# BUCK_Converter.net
KiCad netlist of a schematic drawn in Altium Designer
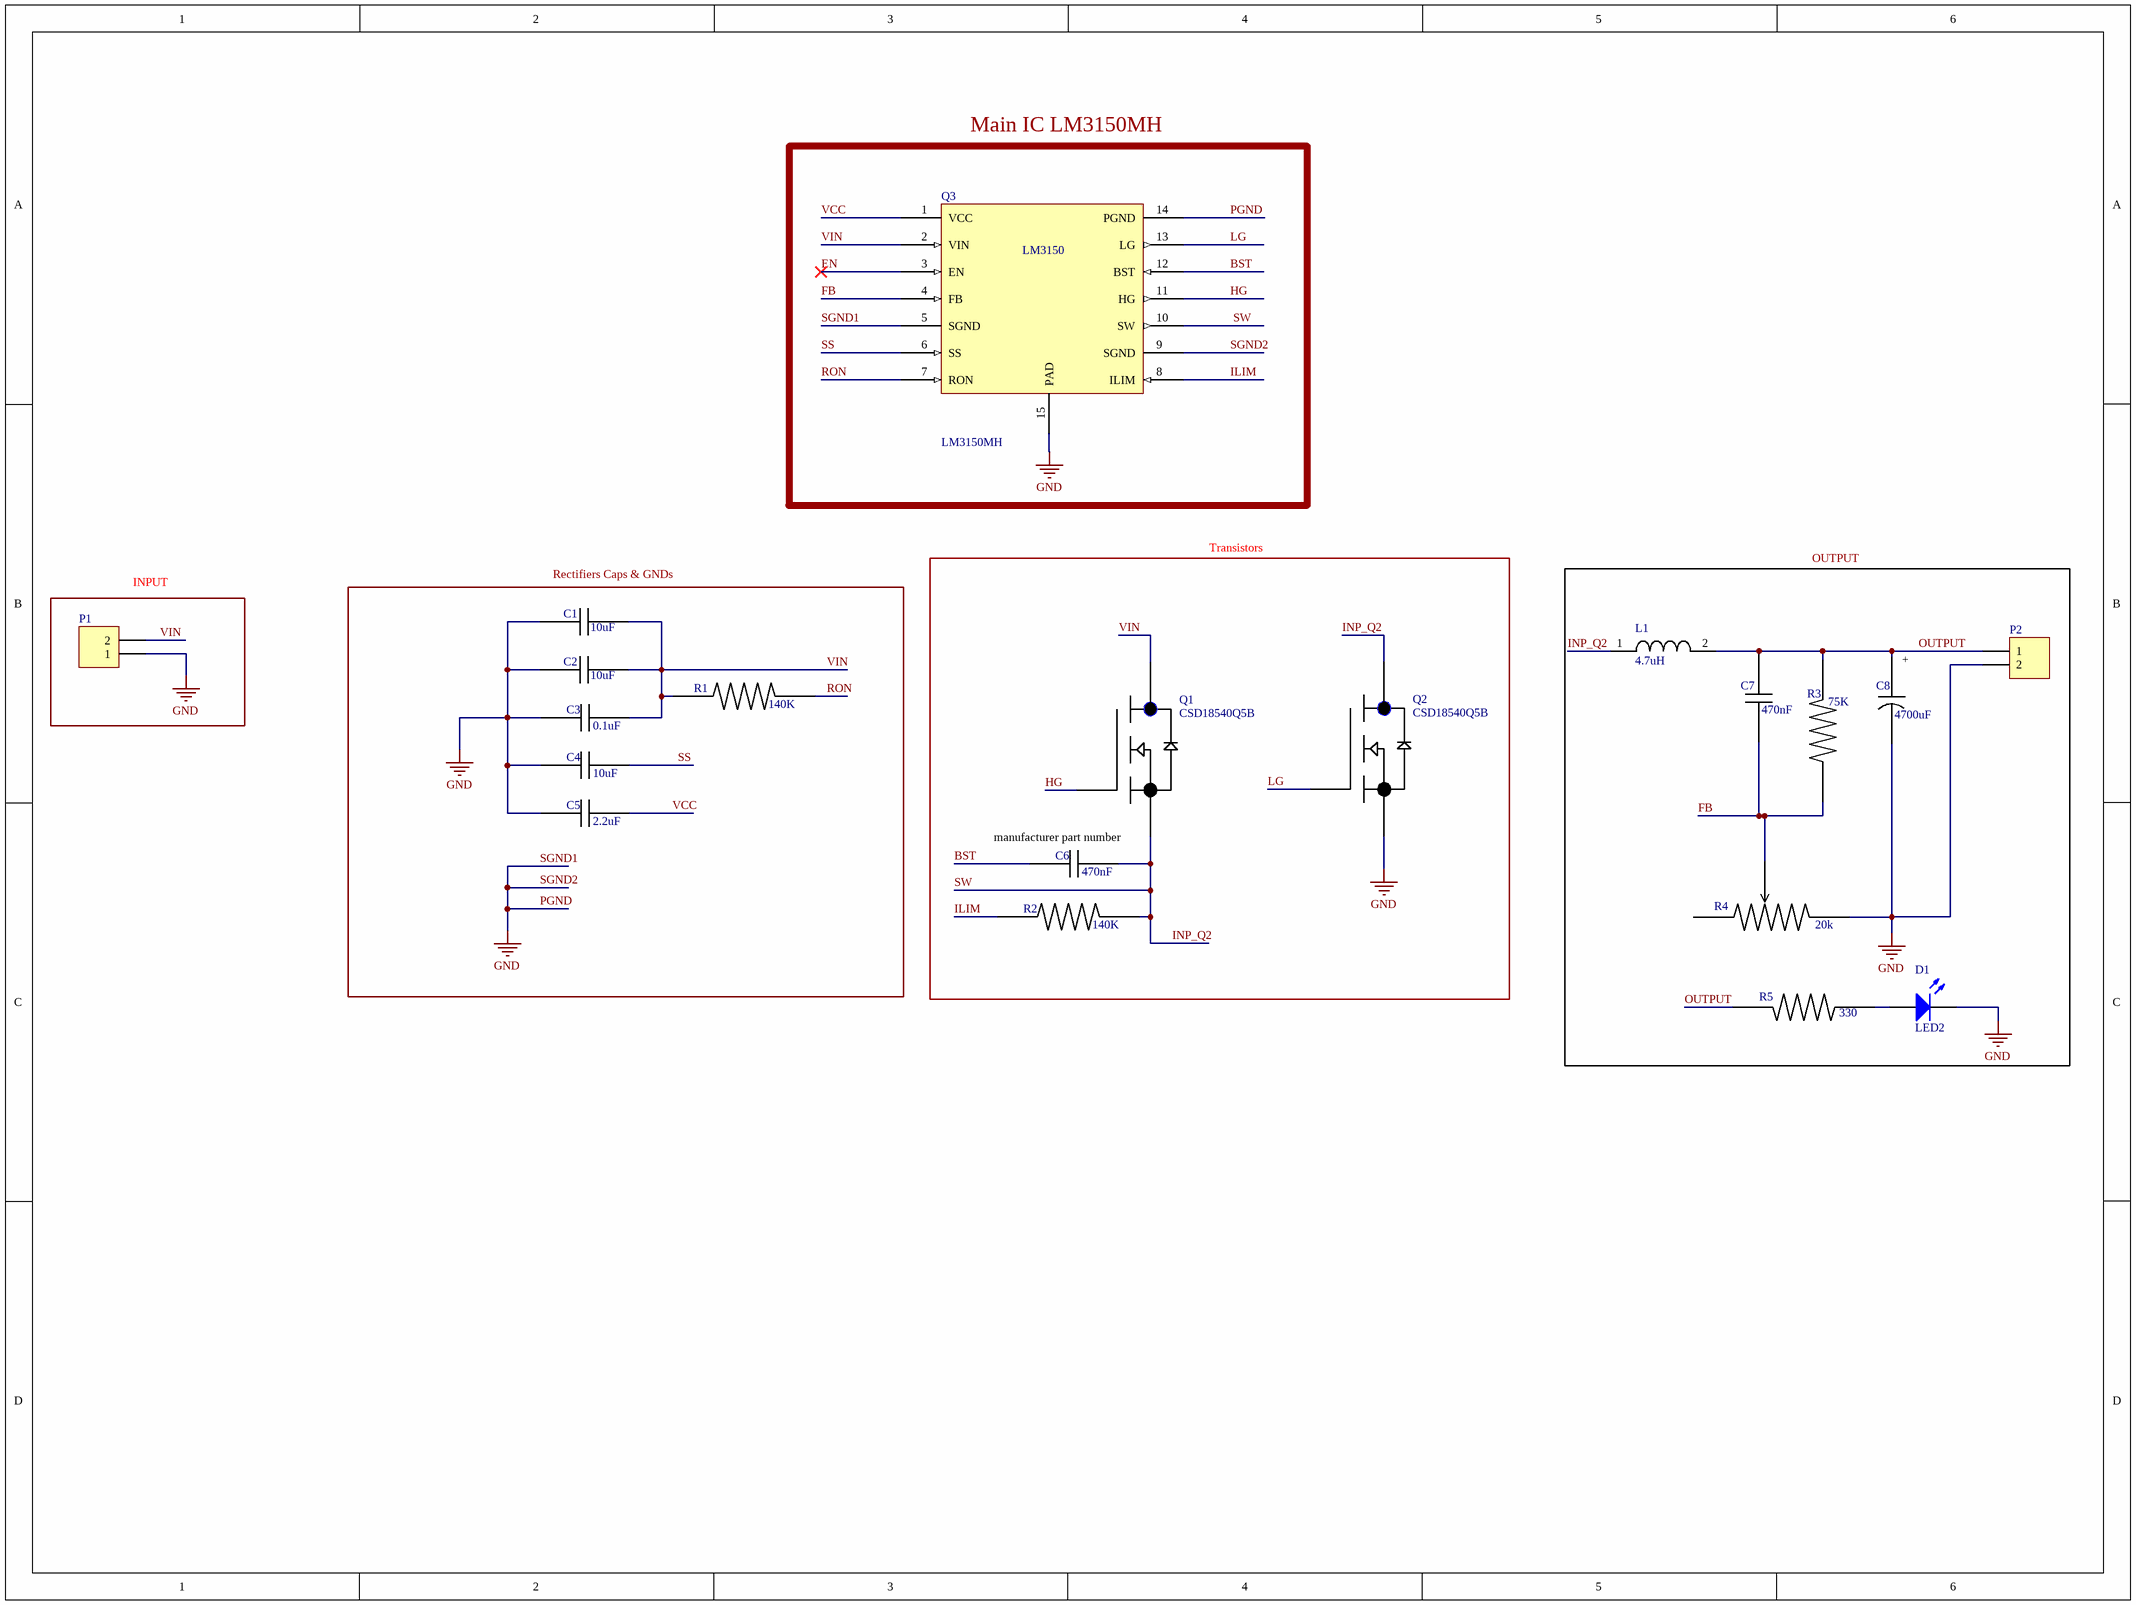
[diagram p0: BUCK_Converter.SchDoc]

(export (version "E")
  (design (tool "Eeschema 10.0.6"))
  (components
    (comp (ref "C1")
      (value "10uF")
      (footprint "1206_cap")
      (description "CAP CER 10UF 16V X5R 1206")
      (fields (field (name "MF") "Samsung Electro-Mechanics"))
      (libsource (lib "components_for_last_time") (part "Capacitor"))
    )
    (comp (ref "C2")
      (value "10uF")
      (footprint "1206_cap")
      (description "CAP CER 10UF 16V X5R 1206")
      (fields (field (name "MF") "Samsung Electro-Mechanics"))
      (libsource (lib "components_for_last_time") (part "Capacitor"))
    )
    (comp (ref "C3")
      (value "0.1uF")
      (footprint "1206_cap")
      (description "CAP CER 0.1UF 50V X7R 1206")
      (fields (field (name "MF") "Samsung Electro-Mechanics"))
      (libsource (lib "Buck comp.") (part "Capacitor_smd"))
    )
    (comp (ref "C4")
      (value "10uF")
      (footprint "1206_cap")
      (description "CAP CER 10UF 16V X5R 1206")
      (fields (field (name "MF") "Samsung Electro-Mechanics"))
      (libsource (lib "Buck comp.") (part "Capacitor_smd"))
    )
    (comp (ref "C5")
      (value "2.2uF")
      (footprint "1206_cap")
      (description "CAP CER 2.2UF 16V X7R 1206")
      (fields (field (name "MF") "Samsung Electro-Mechanics"))
      (libsource (lib "Buck comp.") (part "Capacitor_smd"))
    )
    (comp (ref "C6")
      (value "470nF")
      (footprint "1206_cap")
      (description "CAP CER 0.047UF 50V X7R 1206")
      (fields (field (name "MF") "Samsung Electro-Mechanics"))
      (libsource (lib "Buck comp.") (part "Capacitor_smd"))
    )
    (comp (ref "C7")
      (value "470nF")
      (footprint "1206_cap")
      (description "CAP CER 0.047UF 50V X7R 1206")
      (fields (field (name "MF") "Samsung Electro-Mechanics"))
      (libsource (lib "Buck comp.") (part "Capacitor_smd"))
    )
    (comp (ref "C8")
      (value "4700uF")
      (footprint "CAp")
      (description "CAP ALUM 4700UF 20% 10V SMD")
      (fields (field (name "MF") "Panasonic"))
      (libsource (lib "components_for_last_time") (part "Capacitor_al"))
    )
    (comp (ref "D1")
      (value "LED2")
      (footprint "3.2X1.6X1.1")
      (description "Typical RED, GREEN, YELLOW, AMBER GaAs LED")
      (libsource (lib "Miscellaneous Devices") (part "LED2"))
    )
    (comp (ref "L1")
      (value "4.7uH")
      (footprint "coill")
      (description "FIXED IND 4.7UH 3A 40.3 MOHM SMD")
      (fields (field (name "MF") "Taiyo Yuden"))
      (libsource (lib "components_for_last_time") (part "Coil"))
    )
    (comp (ref "P1")
      (value "Header 2")
      (footprint "HDR1X2")
      (description "Header, 2-Pin")
      (libsource (lib "") (part "Header 2_1"))
    )
    (comp (ref "P2")
      (value "Header 2")
      (footprint "HDR1X2")
      (description "Header, 2-Pin")
      (libsource (lib "Miscellaneous Connectors") (part "Header 2"))
    )
    (comp (ref "Q1")
      (value "CSD18540Q5B")
      (footprint "CSD18540Q5B")
      (description "MOSFET N-CH 60V 100A 8VSON")
      (fields (field (name "MF") "Texas Instruments"))
      (libsource (lib "Buck comp.") (part "CSD18540Q5B"))
    )
    (comp (ref "Q2")
      (value "CSD18540Q5B")
      (footprint "CSD18540Q5B")
      (description "MOSFET N-CH 60V 100A 8VSON")
      (fields (field (name "MF") "Texas Instruments"))
      (libsource (lib "Buck comp.") (part "CSD18540Q5B"))
    )
    (comp (ref "Q3")
      (value "LM3150MH")
      (footprint "LM3150MH")
      (description "IC REG CTRLR BUCK 14TSSOP")
      (fields (field (name "MF") "Texas Instruments"))
      (libsource (lib "components_for_last_time") (part "LM3150MH"))
    )
    (comp (ref "R1")
      (value "140K")
      (footprint "1206_res")
      (description "RES SMD 140K OHM 1% 1/4W 1206")
      (fields (field (name "MF") "Vishay Dale"))
      (libsource (lib "Buck comp.") (part "resistor_smd"))
    )
    (comp (ref "R2")
      (value "140K")
      (footprint "1206_res")
      (description "RES SMD 140K OHM 1% 1/4W 1206")
      (fields (field (name "MF") "Vishay Dale"))
      (libsource (lib "Buck comp.") (part "resistor_smd"))
    )
    (comp (ref "R3")
      (value "75K")
      (footprint "1206_res")
      (description "RES SMD 75K OHM 1% 1/20W 0201")
      (fields (field (name "MF") "Vishay Dale"))
      (libsource (lib "Buck comp.") (part "resistor_smd"))
    )
    (comp (ref "R4")
      (value "20k")
      (footprint "pot_smd")
      (description "20 kOhms 0.5W, 1/2W Gull Wing Surface Mount Trimmer Potentiometer Cermet 1.0 Turn Top Adjustment")
      (fields (field (name "MF") "Bourns Inc."))
      (libsource (lib "components_for_last_time") (part "pot"))
    )
    (comp (ref "R5")
      (value "330")
      (footprint "1206_res")
      (description "RES SMD 330 OHM 1% 1/20W 0201")
      (fields (field (name "MF") "Vishay Dale"))
      (libsource (lib "Buck comp.") (part "resistor_smd"))
    )
  )
  (nets
    (net (code "1") (name "/BST") (class "Default")
      (node (ref "C6") (pin "1") (pinfunction "+_1") (pintype "passive"))
      (node (ref "Q3") (pin "12") (pinfunction "BST_12") (pintype "input"))
    )
    (net (code "2") (name "/EN") (class "Default")
      (node (ref "Q3") (pin "3") (pinfunction "EN_3") (pintype "input+no_connect"))
    )
    (net (code "3") (name "/FB") (class "Default")
      (node (ref "C7") (pin "1") (pinfunction "+_1") (pintype "passive"))
      (node (ref "Q3") (pin "4") (pinfunction "FB_4") (pintype "input"))
      (node (ref "R3") (pin "1") (pintype "passive"))
      (node (ref "R4") (pin "2") (pintype "passive"))
    )
    (net (code "4") (name "/HG") (class "Default")
      (node (ref "Q1") (pin "2") (pintype "passive"))
      (node (ref "Q3") (pin "11") (pinfunction "HG_11") (pintype "output"))
    )
    (net (code "5") (name "/ILIM") (class "Default")
      (node (ref "Q3") (pin "8") (pinfunction "ILIM_8") (pintype "input"))
      (node (ref "R2") (pin "1") (pintype "passive"))
    )
    (net (code "6") (name "/INP_Q2") (class "Default")
      (node (ref "C6") (pin "2") (pinfunction "-_2") (pintype "passive"))
      (node (ref "L1") (pin "1") (pintype "passive"))
      (node (ref "Q1") (pin "1") (pintype "passive"))
      (node (ref "Q2") (pin "3") (pintype "passive"))
      (node (ref "Q3") (pin "10") (pinfunction "SW_10") (pintype "output"))
      (node (ref "R2") (pin "2") (pintype "passive"))
    )
    (net (code "7") (name "/LG") (class "Default")
      (node (ref "Q2") (pin "2") (pintype "passive"))
      (node (ref "Q3") (pin "13") (pinfunction "LG_13") (pintype "output"))
    )
    (net (code "8") (name "/OUTPUT") (class "Default")
      (node (ref "C7") (pin "2") (pinfunction "-_2") (pintype "passive"))
      (node (ref "C8") (pin "1") (pinfunction "+_1") (pintype "passive"))
      (node (ref "L1") (pin "2") (pintype "passive"))
      (node (ref "P2") (pin "1") (pinfunction "1_1") (pintype "passive"))
      (node (ref "R3") (pin "2") (pintype "passive"))
      (node (ref "R5") (pin "2") (pintype "passive"))
    )
    (net (code "9") (name "/RON") (class "Default")
      (node (ref "Q3") (pin "7") (pinfunction "RON_7") (pintype "input"))
      (node (ref "R1") (pin "2") (pintype "passive"))
    )
    (net (code "10") (name "/SS") (class "Default")
      (node (ref "C4") (pin "2") (pinfunction "-_2") (pintype "passive"))
      (node (ref "Q3") (pin "6") (pinfunction "SS_6") (pintype "input"))
    )
    (net (code "11") (name "/VCC") (class "Default")
      (node (ref "C5") (pin "2") (pinfunction "-_2") (pintype "passive"))
      (node (ref "Q3") (pin "1") (pinfunction "VCC_1") (pintype "power_in"))
    )
    (net (code "12") (name "/VIN") (class "Default")
      (node (ref "C1") (pin "2") (pinfunction "-_2") (pintype "passive"))
      (node (ref "C2") (pin "2") (pinfunction "-_2") (pintype "passive"))
      (node (ref "C3") (pin "1") (pinfunction "+_1") (pintype "passive"))
      (node (ref "P1") (pin "2") (pinfunction "2_2") (pintype "passive"))
      (node (ref "Q1") (pin "3") (pintype "passive"))
      (node (ref "Q3") (pin "2") (pinfunction "VIN_2") (pintype "input"))
      (node (ref "R1") (pin "1") (pintype "passive"))
    )
    (net (code "13") (name "GND") (class "Default")
      (node (ref "C1") (pin "1") (pinfunction "+_1") (pintype "passive"))
      (node (ref "C2") (pin "1") (pinfunction "+_1") (pintype "passive"))
      (node (ref "C3") (pin "2") (pinfunction "-_2") (pintype "passive"))
      (node (ref "C4") (pin "1") (pinfunction "+_1") (pintype "passive"))
      (node (ref "C5") (pin "1") (pinfunction "+_1") (pintype "passive"))
      (node (ref "C8") (pin "2") (pinfunction "-_2") (pintype "passive"))
      (node (ref "D1") (pin "2") (pinfunction "K_2") (pintype "passive"))
      (node (ref "P1") (pin "1") (pinfunction "1_1") (pintype "passive"))
      (node (ref "P2") (pin "2") (pinfunction "2_2") (pintype "passive"))
      (node (ref "Q2") (pin "1") (pintype "passive"))
      (node (ref "Q3") (pin "14") (pinfunction "PGND_14") (pintype "passive"))
      (node (ref "Q3") (pin "15") (pinfunction "PAD_15") (pintype "passive"))
      (node (ref "Q3") (pin "5") (pinfunction "SGND_5") (pintype "passive"))
      (node (ref "Q3") (pin "9") (pinfunction "SGND_9") (pintype "passive"))
      (node (ref "R4") (pin "3") (pintype "passive"))
    )
    (net (code "14") (name "Net-(D1-A)") (class "Default")
      (node (ref "D1") (pin "1") (pinfunction "A_1") (pintype "passive"))
      (node (ref "R5") (pin "1") (pintype "passive"))
    )
    (net (code "15") (name "unconnected-(R4-Pad1)") (class "Default")
      (node (ref "R4") (pin "1") (pintype "passive"))
    )
  )
)
